# TamagotchiMainBoard.net
KiCad netlist of a schematic drawn in Altium Designer
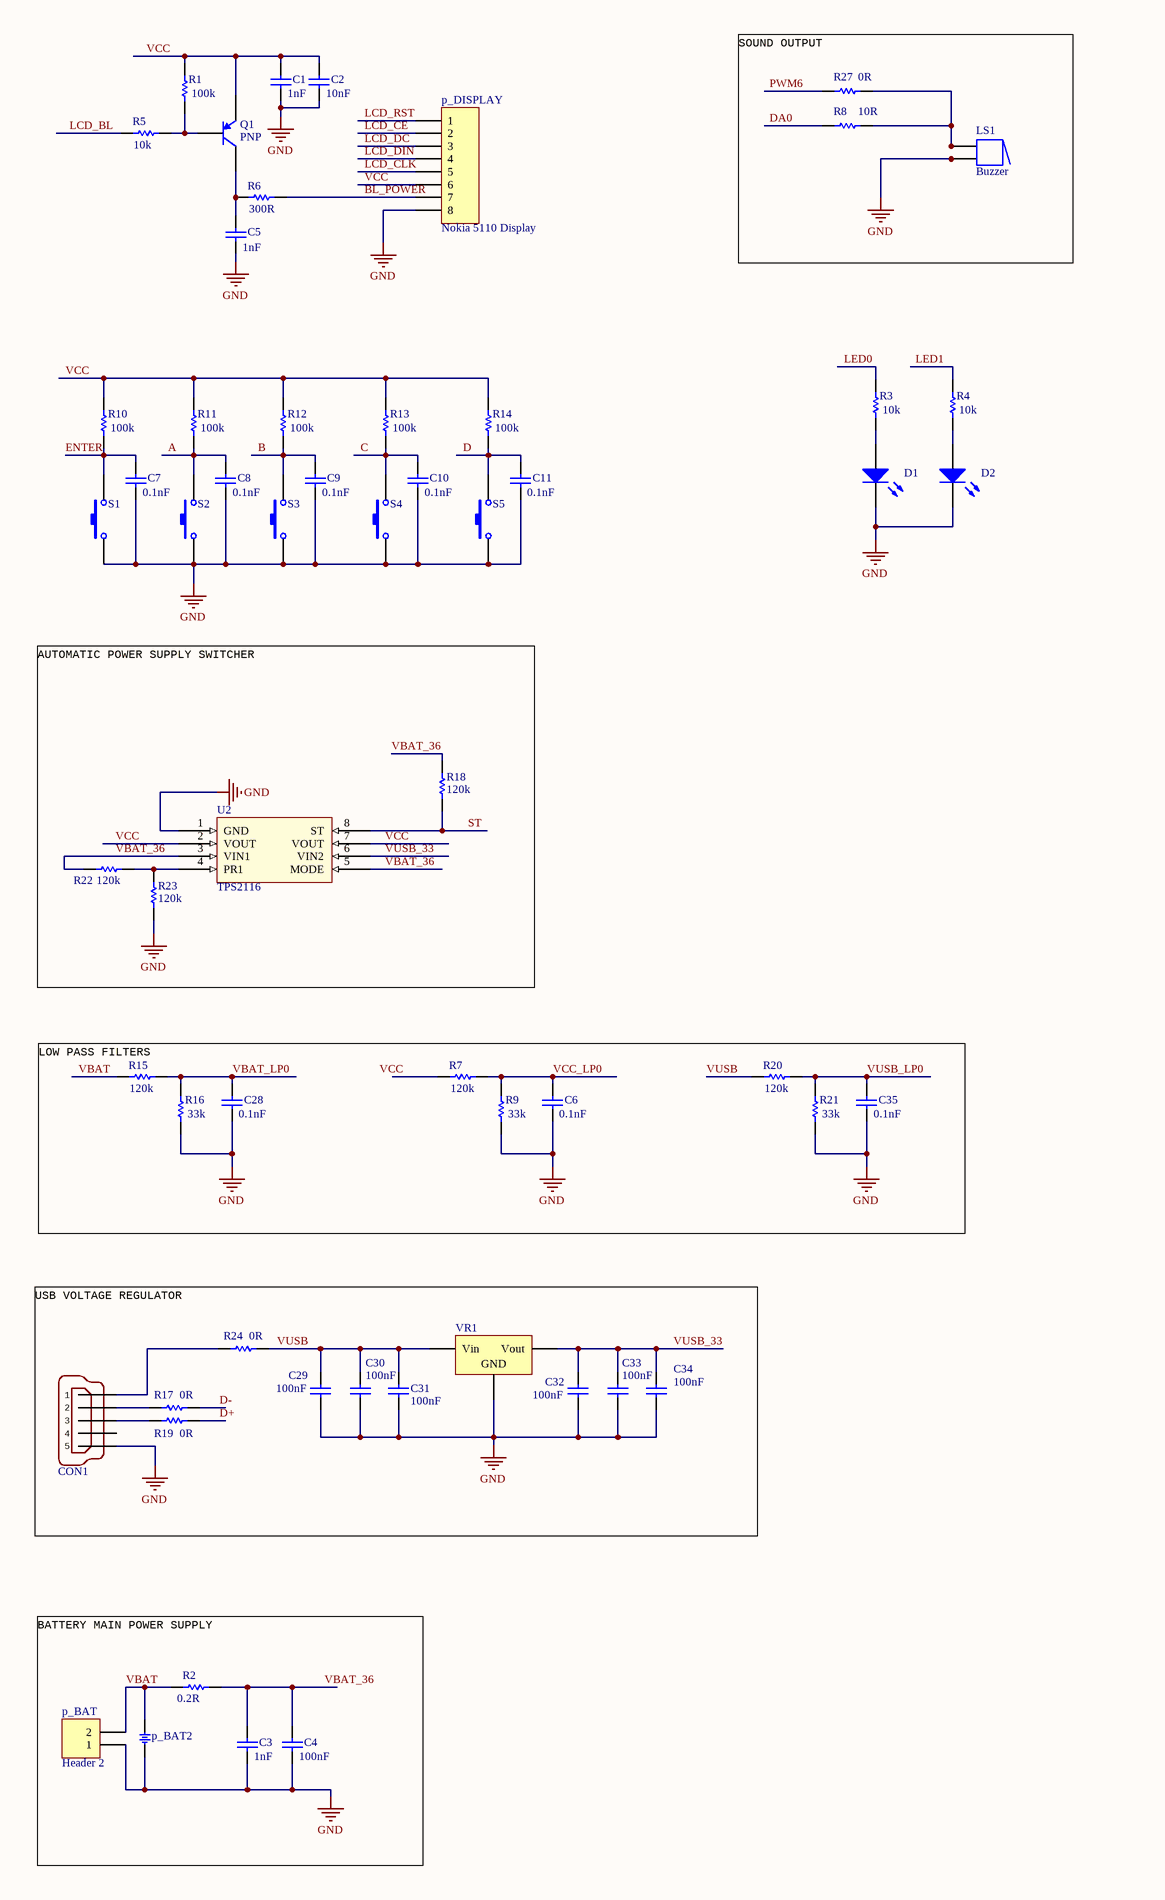
[diagram p0: TamagotchiMainBoard.SchDoc, left]
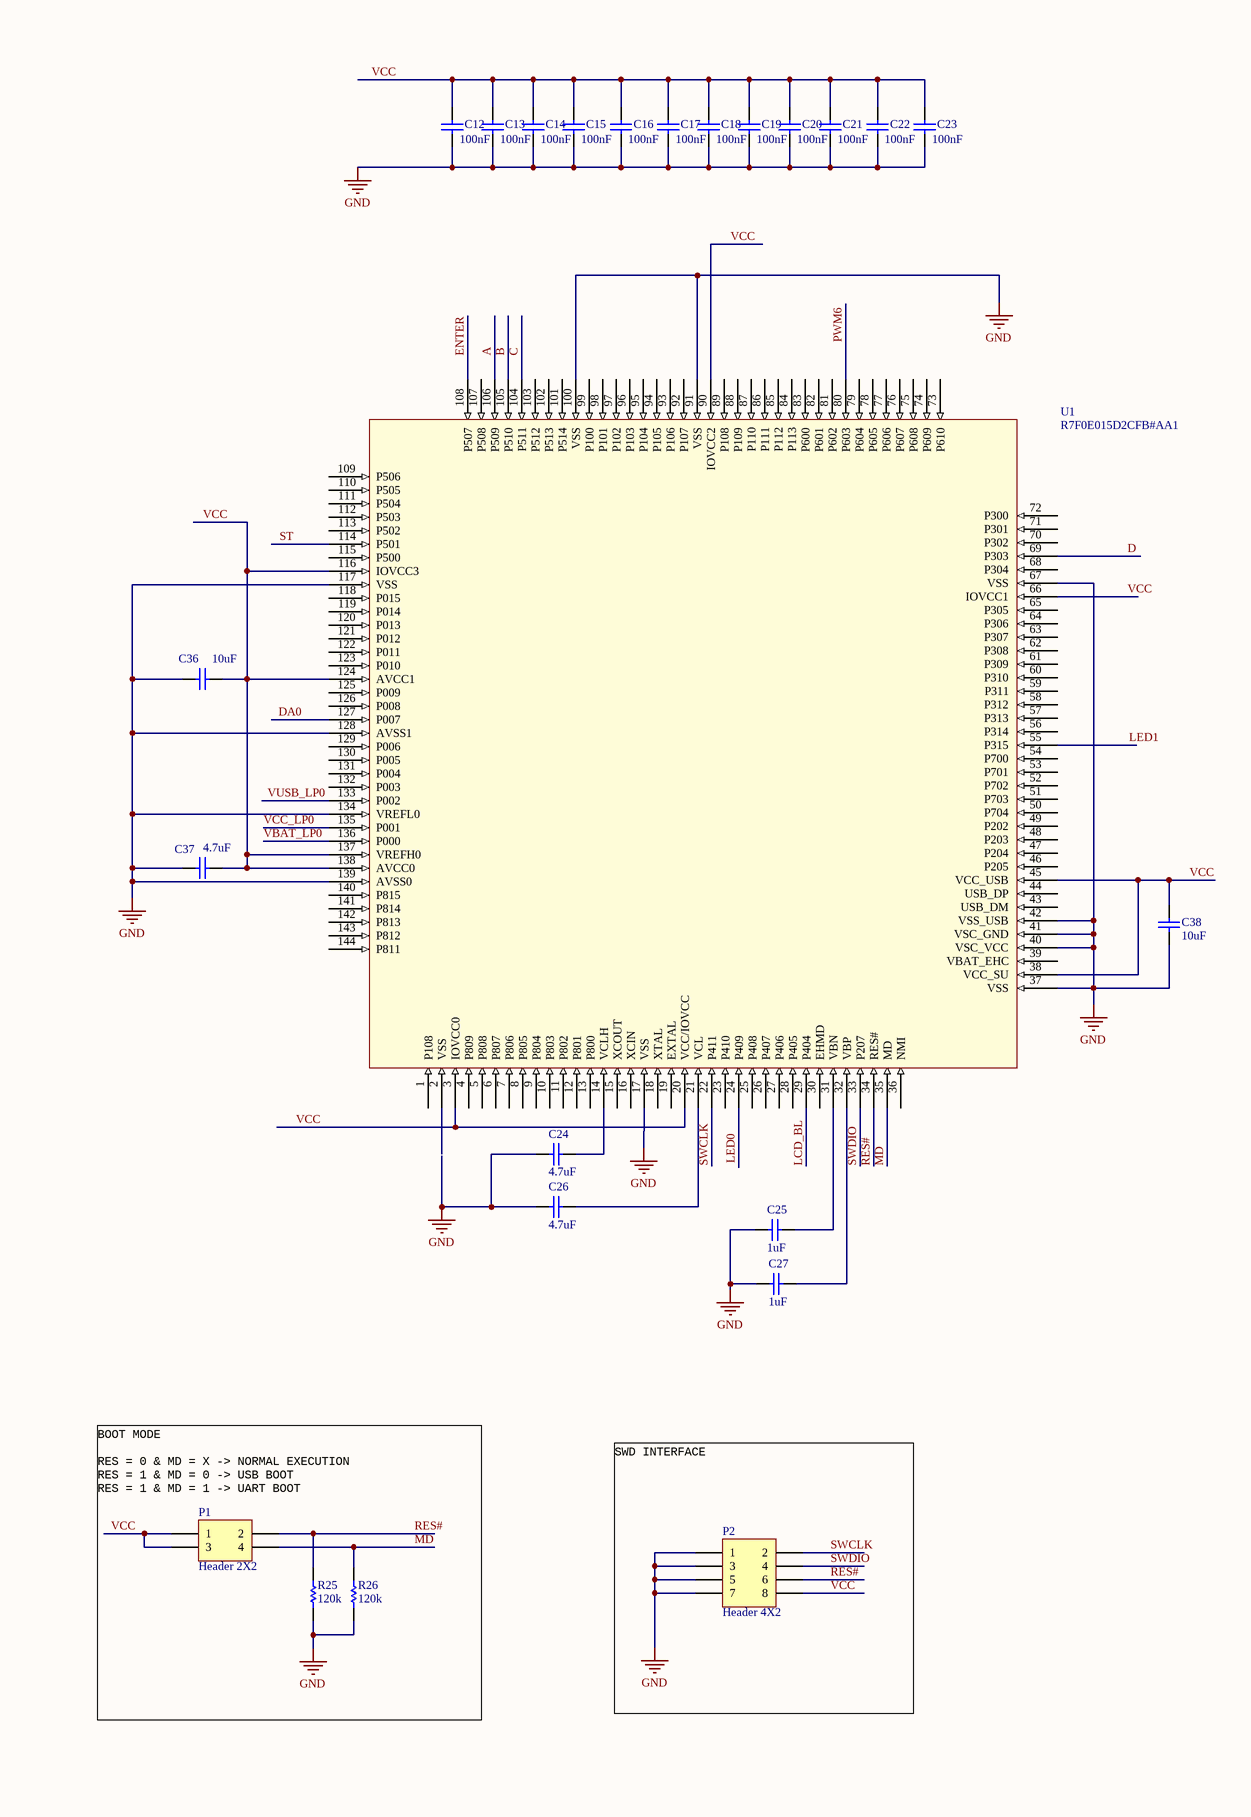
[diagram p1: TamagotchiMainBoard.SchDoc, right]

(export (version "E")
  (design (tool "Eeschema 10.0.6"))
  (components
    (comp (ref "C1")
      (value "1nF")
      (footprint "Miscellaneous Devices:C0805")
      (description "Capacitor")
      (fields (field (name "Comment") "Cap"))
      (libsource (lib "Miscellaneous Devices") (part "Cap"))
    )
    (comp (ref "C2")
      (value "10nF")
      (footprint "Miscellaneous Devices:C0805")
      (description "Capacitor")
      (fields (field (name "Comment") "Cap"))
      (libsource (lib "Miscellaneous Devices") (part "Cap"))
    )
    (comp (ref "C3")
      (value "1nF")
      (footprint "Miscellaneous Devices:C0805")
      (description "Capacitor")
      (fields (field (name "Comment") "Cap"))
      (libsource (lib "Miscellaneous Devices") (part "Cap"))
    )
    (comp (ref "C4")
      (value "100nF")
      (footprint "Miscellaneous Devices:C0805")
      (description "Capacitor")
      (fields (field (name "Comment") "Cap"))
      (libsource (lib "Miscellaneous Devices") (part "Cap"))
    )
    (comp (ref "C5")
      (value "1nF")
      (footprint "Miscellaneous Devices:C0805")
      (description "Capacitor")
      (fields (field (name "Comment") "Cap"))
      (libsource (lib "Miscellaneous Devices") (part "Cap"))
    )
    (comp (ref "C6")
      (value "0.1nF")
      (footprint "Miscellaneous Devices:C0805")
      (description "Capacitor")
      (fields (field (name "Comment") "Cap"))
      (libsource (lib "Miscellaneous Devices") (part "Cap"))
    )
    (comp (ref "C7")
      (value "0.1nF")
      (footprint "Miscellaneous Devices:C0805")
      (description "Capacitor")
      (fields (field (name "Comment") "Cap"))
      (libsource (lib "Miscellaneous Devices") (part "Cap"))
    )
    (comp (ref "C8")
      (value "0.1nF")
      (footprint "Miscellaneous Devices:C0805")
      (description "Capacitor")
      (fields (field (name "Comment") "Cap"))
      (libsource (lib "Miscellaneous Devices") (part "Cap"))
    )
    (comp (ref "C9")
      (value "0.1nF")
      (footprint "Miscellaneous Devices:C0805")
      (description "Capacitor")
      (fields (field (name "Comment") "Cap"))
      (libsource (lib "Miscellaneous Devices") (part "Cap"))
    )
    (comp (ref "C10")
      (value "0.1nF")
      (footprint "Miscellaneous Devices:C0805")
      (description "Capacitor")
      (fields (field (name "Comment") "Cap"))
      (libsource (lib "Miscellaneous Devices") (part "Cap"))
    )
    (comp (ref "C11")
      (value "0.1nF")
      (footprint "Miscellaneous Devices:C0805")
      (description "Capacitor")
      (fields (field (name "Comment") "Cap"))
      (libsource (lib "Miscellaneous Devices") (part "Cap"))
    )
    (comp (ref "C12")
      (value "100nF")
      (footprint "Miscellaneous Devices:C0805")
      (description "Capacitor")
      (fields (field (name "Comment") "Cap"))
      (libsource (lib "Miscellaneous Devices") (part "Cap"))
    )
    (comp (ref "C13")
      (value "100nF")
      (footprint "Miscellaneous Devices:C0805")
      (description "Capacitor")
      (fields (field (name "Comment") "Cap"))
      (libsource (lib "Miscellaneous Devices") (part "Cap"))
    )
    (comp (ref "C14")
      (value "100nF")
      (footprint "Miscellaneous Devices:C0805")
      (description "Capacitor")
      (fields (field (name "Comment") "Cap"))
      (libsource (lib "Miscellaneous Devices") (part "Cap"))
    )
    (comp (ref "C15")
      (value "100nF")
      (footprint "Miscellaneous Devices:C0805")
      (description "Capacitor")
      (fields (field (name "Comment") "Cap"))
      (libsource (lib "Miscellaneous Devices") (part "Cap"))
    )
    (comp (ref "C16")
      (value "100nF")
      (footprint "Miscellaneous Devices:C0805")
      (description "Capacitor")
      (fields (field (name "Comment") "Cap"))
      (libsource (lib "Miscellaneous Devices") (part "Cap"))
    )
    (comp (ref "C17")
      (value "100nF")
      (footprint "Miscellaneous Devices:C0805")
      (description "Capacitor")
      (fields (field (name "Comment") "Cap"))
      (libsource (lib "Miscellaneous Devices") (part "Cap"))
    )
    (comp (ref "C18")
      (value "100nF")
      (footprint "Miscellaneous Devices:C0805")
      (description "Capacitor")
      (fields (field (name "Comment") "Cap"))
      (libsource (lib "Miscellaneous Devices") (part "Cap"))
    )
    (comp (ref "C19")
      (value "100nF")
      (footprint "Miscellaneous Devices:C0805")
      (description "Capacitor")
      (fields (field (name "Comment") "Cap"))
      (libsource (lib "Miscellaneous Devices") (part "Cap"))
    )
    (comp (ref "C20")
      (value "100nF")
      (footprint "Miscellaneous Devices:C0805")
      (description "Capacitor")
      (fields (field (name "Comment") "Cap"))
      (libsource (lib "Miscellaneous Devices") (part "Cap"))
    )
    (comp (ref "C21")
      (value "100nF")
      (footprint "Miscellaneous Devices:C0805")
      (description "Capacitor")
      (fields (field (name "Comment") "Cap"))
      (libsource (lib "Miscellaneous Devices") (part "Cap"))
    )
    (comp (ref "C22")
      (value "100nF")
      (footprint "Miscellaneous Devices:C0805")
      (description "Capacitor")
      (fields (field (name "Comment") "Cap"))
      (libsource (lib "Miscellaneous Devices") (part "Cap"))
    )
    (comp (ref "C23")
      (value "100nF")
      (footprint "Miscellaneous Devices:C0805")
      (description "Capacitor")
      (fields (field (name "Comment") "Cap"))
      (libsource (lib "Miscellaneous Devices") (part "Cap"))
    )
    (comp (ref "C24")
      (value "4.7uF")
      (footprint "Miscellaneous Devices:C1206")
      (description "Capacitor")
      (fields (field (name "Comment") "Cap"))
      (libsource (lib "Miscellaneous Devices") (part "Cap"))
    )
    (comp (ref "C25")
      (value "1uF")
      (footprint "Miscellaneous Devices:C0805")
      (description "Capacitor")
      (fields (field (name "Comment") "Cap"))
      (libsource (lib "Miscellaneous Devices") (part "Cap"))
    )
    (comp (ref "C26")
      (value "4.7uF")
      (footprint "Miscellaneous Devices:C1206")
      (description "Capacitor")
      (fields (field (name "Comment") "Cap"))
      (libsource (lib "Miscellaneous Devices") (part "Cap"))
    )
    (comp (ref "C27")
      (value "1uF")
      (footprint "Miscellaneous Devices:C0805")
      (description "Capacitor")
      (fields (field (name "Comment") "Cap"))
      (libsource (lib "Miscellaneous Devices") (part "Cap"))
    )
    (comp (ref "C28")
      (value "0.1nF")
      (footprint "Miscellaneous Devices:C0805")
      (description "Capacitor")
      (fields (field (name "Comment") "Cap"))
      (libsource (lib "Miscellaneous Devices") (part "Cap"))
    )
    (comp (ref "C29")
      (value "100nF")
      (footprint "Miscellaneous Devices:C0805")
      (description "Capacitor")
      (fields (field (name "Comment") "Cap"))
      (libsource (lib "Miscellaneous Devices") (part "Cap"))
    )
    (comp (ref "C30")
      (value "100nF")
      (footprint "Miscellaneous Devices:C0805")
      (description "Capacitor")
      (fields (field (name "Comment") "Cap"))
      (libsource (lib "Miscellaneous Devices") (part "Cap"))
    )
    (comp (ref "C31")
      (value "100nF")
      (footprint "Miscellaneous Devices:C0805")
      (description "Capacitor")
      (fields (field (name "Comment") "Cap"))
      (libsource (lib "Miscellaneous Devices") (part "Cap"))
    )
    (comp (ref "C32")
      (value "100nF")
      (footprint "Miscellaneous Devices:C0805")
      (description "Capacitor")
      (fields (field (name "Comment") "Cap"))
      (libsource (lib "Miscellaneous Devices") (part "Cap"))
    )
    (comp (ref "C33")
      (value "100nF")
      (footprint "Miscellaneous Devices:C0805")
      (description "Capacitor")
      (fields (field (name "Comment") "Cap"))
      (libsource (lib "Miscellaneous Devices") (part "Cap"))
    )
    (comp (ref "C34")
      (value "100nF")
      (footprint "Miscellaneous Devices:C0805")
      (description "Capacitor")
      (fields (field (name "Comment") "Cap"))
      (libsource (lib "Miscellaneous Devices") (part "Cap"))
    )
    (comp (ref "C35")
      (value "0.1nF")
      (footprint "Miscellaneous Devices:C0805")
      (description "Capacitor")
      (fields (field (name "Comment") "Cap"))
      (libsource (lib "Miscellaneous Devices") (part "Cap"))
    )
    (comp (ref "C36")
      (value "10uF")
      (footprint "Miscellaneous Devices:C1206")
      (description "Capacitor")
      (fields (field (name "Comment") "Cap"))
      (libsource (lib "Miscellaneous Devices") (part "Cap"))
    )
    (comp (ref "C37")
      (value "4.7uF")
      (footprint "Miscellaneous Devices:C1206")
      (description "Capacitor")
      (fields (field (name "Comment") "Cap"))
      (libsource (lib "Miscellaneous Devices") (part "Cap"))
    )
    (comp (ref "C38")
      (value "10uF")
      (footprint "Miscellaneous Devices:C1206")
      (description "Capacitor")
      (fields (field (name "Comment") "Cap"))
      (libsource (lib "Miscellaneous Devices") (part "Cap"))
    )
    (comp (ref "CON1")
      (value "897-43-005-00-100001")
      (footprint "USB-MINI-B-5P-SMD")
      (description "Connector,MiniUSB B port,5 position,Right Angle,Gold flash 30u,black,SMD")
      (fields (field (name "MANUFACTURER") "MILL-MAX"))
      (libsource (lib "LAUNCHXL-F28379D_REV2.0") (part "MINI-USB-32005-201"))
    )
    (comp (ref "D1")
      (value "LED0")
      (description "Typical INFRARED GaAs LED")
      (libsource (lib "Miscellaneous Devices") (part "LED0"))
    )
    (comp (ref "D2")
      (value "LED0")
      (description "Typical INFRARED GaAs LED")
      (libsource (lib "Miscellaneous Devices") (part "LED0"))
    )
    (comp (ref "LS1")
      (value "Buzzer")
      (footprint "HDR1X2")
      (description "Magnetic Transducer Buzzer")
      (libsource (lib "Miscellaneous Devices") (part "Buzzer"))
    )
    (comp (ref "P1")
      (value "Header 2X2")
      (footprint "HDR2X2")
      (description "Header, 2-Pin, Dual row")
      (libsource (lib "Miscellaneous Connectors") (part "Header 2X2"))
    )
    (comp (ref "P2")
      (value "Header 4X2")
      (footprint "HDR2X4")
      (description "Header, 4-Pin, Dual row")
      (libsource (lib "Miscellaneous Connectors") (part "Header 4X2"))
    )
    (comp (ref "p_BAT")
      (value "Header 2")
      (footprint "HDR1X2")
      (description "Header, 2-Pin")
      (libsource (lib "Miscellaneous Connectors") (part "Header 2"))
    )
    (comp (ref "p_BAT2")
      (value "~")
      (footprint "BTH2032")
      (description "BATTERY HOLDER, CR2032")
      (libsource (lib "BTH2032") (part "BATH_CR2032"))
    )
    (comp (ref "p_DISPLAY")
      (value "Nokia 5110 Display")
      (footprint "HDR1X8")
      (description "Header, 8-Pin")
      (libsource (lib "Miscellaneous Connectors") (part "Header 8"))
    )
    (comp (ref "Q1")
      (value "PNP")
      (footprint "SOT-23B_N")
      (description "PNP Bipolar Transistor")
      (libsource (lib "Miscellaneous Devices") (part "PNP"))
    )
    (comp (ref "R1")
      (value "100k")
      (footprint "6-0805_M")
      (description "Resistor")
      (fields (field (name "Comment") "Res1"))
      (libsource (lib "Miscellaneous Devices") (part "Res1"))
    )
    (comp (ref "R2")
      (value "0.2R")
      (footprint "6-0805_M")
      (description "Resistor")
      (fields (field (name "Comment") "Res1"))
      (libsource (lib "Miscellaneous Devices") (part "Res1"))
    )
    (comp (ref "R3")
      (value "10k")
      (footprint "6-0805_M")
      (description "Resistor")
      (fields (field (name "Comment") "Res1"))
      (libsource (lib "Miscellaneous Devices") (part "Res1"))
    )
    (comp (ref "R4")
      (value "10k")
      (footprint "6-0805_M")
      (description "Resistor")
      (fields (field (name "Comment") "Res1"))
      (libsource (lib "Miscellaneous Devices") (part "Res1"))
    )
    (comp (ref "R5")
      (value "10k")
      (footprint "6-0805_M")
      (description "Resistor")
      (fields (field (name "Comment") "Res1"))
      (libsource (lib "Miscellaneous Devices") (part "Res1"))
    )
    (comp (ref "R6")
      (value "300R")
      (footprint "6-0805_M")
      (description "Resistor")
      (fields (field (name "Comment") "Res1"))
      (libsource (lib "Miscellaneous Devices") (part "Res1"))
    )
    (comp (ref "R7")
      (value "120k")
      (footprint "6-0805_M")
      (description "Resistor")
      (fields (field (name "Comment") "Res1"))
      (libsource (lib "Miscellaneous Devices") (part "Res1"))
    )
    (comp (ref "R8")
      (value "10R")
      (footprint "6-0805_M")
      (description "Resistor")
      (fields (field (name "Comment") "Res1"))
      (libsource (lib "Miscellaneous Devices") (part "Res1"))
    )
    (comp (ref "R9")
      (value "33k")
      (footprint "6-0805_M")
      (description "Resistor")
      (fields (field (name "Comment") "Res1"))
      (libsource (lib "Miscellaneous Devices") (part "Res1"))
    )
    (comp (ref "R10")
      (value "100k")
      (footprint "6-0805_M")
      (description "Resistor")
      (fields (field (name "Comment") "Res1"))
      (libsource (lib "Miscellaneous Devices") (part "Res1"))
    )
    (comp (ref "R11")
      (value "100k")
      (footprint "6-0805_M")
      (description "Resistor")
      (fields (field (name "Comment") "Res1"))
      (libsource (lib "Miscellaneous Devices") (part "Res1"))
    )
    (comp (ref "R12")
      (value "100k")
      (footprint "6-0805_M")
      (description "Resistor")
      (fields (field (name "Comment") "Res1"))
      (libsource (lib "Miscellaneous Devices") (part "Res1"))
    )
    (comp (ref "R13")
      (value "100k")
      (footprint "6-0805_M")
      (description "Resistor")
      (fields (field (name "Comment") "Res1"))
      (libsource (lib "Miscellaneous Devices") (part "Res1"))
    )
    (comp (ref "R14")
      (value "100k")
      (footprint "6-0805_M")
      (description "Resistor")
      (fields (field (name "Comment") "Res1"))
      (libsource (lib "Miscellaneous Devices") (part "Res1"))
    )
    (comp (ref "R15")
      (value "120k")
      (footprint "6-0805_M")
      (description "Resistor")
      (fields (field (name "Comment") "Res1"))
      (libsource (lib "Miscellaneous Devices") (part "Res1"))
    )
    (comp (ref "R16")
      (value "33k")
      (footprint "6-0805_M")
      (description "Resistor")
      (fields (field (name "Comment") "Res1"))
      (libsource (lib "Miscellaneous Devices") (part "Res1"))
    )
    (comp (ref "R17")
      (value "0R")
      (footprint "6-0805_M")
      (description "Resistor")
      (libsource (lib "Miscellaneous Devices") (part "Res1"))
    )
    (comp (ref "R18")
      (value "120k")
      (footprint "6-0805_M")
      (description "Resistor")
      (fields (field (name "Comment") "Res1"))
      (libsource (lib "Miscellaneous Devices") (part "Res1"))
    )
    (comp (ref "R19")
      (value "0R")
      (footprint "6-0805_M")
      (description "Resistor")
      (libsource (lib "Miscellaneous Devices") (part "Res1"))
    )
    (comp (ref "R20")
      (value "120k")
      (footprint "6-0805_M")
      (description "Resistor")
      (fields (field (name "Comment") "Res1"))
      (libsource (lib "Miscellaneous Devices") (part "Res1"))
    )
    (comp (ref "R21")
      (value "33k")
      (footprint "6-0805_M")
      (description "Resistor")
      (fields (field (name "Comment") "Res1"))
      (libsource (lib "Miscellaneous Devices") (part "Res1"))
    )
    (comp (ref "R22")
      (value "120k")
      (footprint "6-0805_M")
      (description "Resistor")
      (fields (field (name "Comment") "Res1"))
      (libsource (lib "Miscellaneous Devices") (part "Res1"))
    )
    (comp (ref "R23")
      (value "120k")
      (footprint "6-0805_M")
      (description "Resistor")
      (fields (field (name "Comment") "Res1"))
      (libsource (lib "Miscellaneous Devices") (part "Res1"))
    )
    (comp (ref "R24")
      (value "0R")
      (footprint "6-0805_M")
      (description "Resistor")
      (libsource (lib "Miscellaneous Devices") (part "Res1"))
    )
    (comp (ref "R25")
      (value "120k")
      (footprint "6-0805_M")
      (description "Resistor")
      (fields (field (name "Comment") "Res1"))
      (libsource (lib "Miscellaneous Devices") (part "Res1"))
    )
    (comp (ref "R26")
      (value "120k")
      (footprint "6-0805_M")
      (description "Resistor")
      (fields (field (name "Comment") "Res1"))
      (libsource (lib "Miscellaneous Devices") (part "Res1"))
    )
    (comp (ref "R27")
      (value "0R")
      (footprint "6-0805_M")
      (description "Resistor")
      (fields (field (name "Comment") "Res1"))
      (libsource (lib "Miscellaneous Devices") (part "Res1"))
    )
    (comp (ref "S1")
      (value "SW-PB")
      (footprint "SPST-2")
      (description "Switch")
      (libsource (lib "Miscellaneous Devices") (part "SW-PB"))
    )
    (comp (ref "S2")
      (value "SW-PB")
      (footprint "SPST-2")
      (description "Switch")
      (libsource (lib "Miscellaneous Devices") (part "SW-PB"))
    )
    (comp (ref "S3")
      (value "SW-PB")
      (footprint "SPST-2")
      (description "Switch")
      (libsource (lib "Miscellaneous Devices") (part "SW-PB"))
    )
    (comp (ref "S4")
      (value "SW-PB")
      (footprint "SPST-2")
      (description "Switch")
      (libsource (lib "Miscellaneous Devices") (part "SW-PB"))
    )
    (comp (ref "S5")
      (value "SW-PB")
      (footprint "SPST-2")
      (description "Switch")
      (libsource (lib "Miscellaneous Devices") (part "SW-PB"))
    )
    (comp (ref "U1")
      (value "R7F0E015D2CFB#AA1")
      (footprint "SQFP50P2200X2200X170-144N")
      (description "ARM® Cortex®-M0+ series Microcontroller IC 32-Bit 24MHz 1.5MB (1.5M x 8) FLASH 144-LFQFP (20x20)")
      (libsource (lib "YamagotchiLib") (part "R7F0E015D2CFB#AA1"))
    )
    (comp (ref "U2")
      (value "TPS2116")
      (description "TPS2116 1.6 V to 5.5 V, 2.5-A Low IQ Power Mux with Manual and Priority Switchover")
      (libsource (lib "YamagotchiLib") (part "TPS2116"))
    )
    (comp (ref "VR1")
      (value "Volt Reg")
      (footprint "D2PAK_N")
      (description "Voltage Regulator")
      (libsource (lib "Miscellaneous Devices") (part "Volt Reg"))
    )
  )
  (nets
    (net (code "1") (name "/A") (class "Default")
      (node (ref "C8") (pin "1") (pinfunction "1_1") (pintype "passive"))
      (node (ref "R11") (pin "2") (pinfunction "2_2") (pintype "passive"))
      (node (ref "S2") (pin "2") (pinfunction "2_2") (pintype "passive"))
      (node (ref "U1") (pin "106") (pinfunction "P509_106") (pintype "input"))
    )
    (net (code "2") (name "/B") (class "Default")
      (node (ref "C9") (pin "1") (pinfunction "1_1") (pintype "passive"))
      (node (ref "R12") (pin "2") (pinfunction "2_2") (pintype "passive"))
      (node (ref "S3") (pin "2") (pinfunction "2_2") (pintype "passive"))
      (node (ref "U1") (pin "105") (pinfunction "P510_105") (pintype "input"))
    )
    (net (code "3") (name "/BL_POWER") (class "Default")
      (node (ref "R6") (pin "1") (pinfunction "1_1") (pintype "passive"))
      (node (ref "p_DISPLAY") (pin "7") (pinfunction "7_7") (pintype "passive"))
    )
    (net (code "4") (name "/C") (class "Default")
      (node (ref "C10") (pin "1") (pinfunction "1_1") (pintype "passive"))
      (node (ref "R13") (pin "2") (pinfunction "2_2") (pintype "passive"))
      (node (ref "S4") (pin "2") (pinfunction "2_2") (pintype "passive"))
      (node (ref "U1") (pin "104") (pinfunction "P511_104") (pintype "input"))
    )
    (net (code "5") (name "/D") (class "Default")
      (node (ref "C11") (pin "1") (pinfunction "1_1") (pintype "passive"))
      (node (ref "R14") (pin "2") (pinfunction "2_2") (pintype "passive"))
      (node (ref "S5") (pin "2") (pinfunction "2_2") (pintype "passive"))
      (node (ref "U1") (pin "69") (pinfunction "P303_69") (pintype "input"))
    )
    (net (code "6") (name "/D+") (class "Default")
      (node (ref "R19") (pin "1") (pinfunction "1_1") (pintype "passive"))
    )
    (net (code "7") (name "/D-") (class "Default")
      (node (ref "R17") (pin "1") (pinfunction "1_1") (pintype "passive"))
    )
    (net (code "8") (name "/DA0") (class "Default")
      (node (ref "R8") (pin "1") (pinfunction "1_1") (pintype "passive"))
      (node (ref "U1") (pin "127") (pinfunction "P007_127") (pintype "input"))
    )
    (net (code "9") (name "/ENTER") (class "Default")
      (node (ref "C7") (pin "1") (pinfunction "1_1") (pintype "passive"))
      (node (ref "R10") (pin "2") (pinfunction "2_2") (pintype "passive"))
      (node (ref "S1") (pin "2") (pinfunction "2_2") (pintype "passive"))
      (node (ref "U1") (pin "108") (pinfunction "P507_108") (pintype "input"))
    )
    (net (code "10") (name "/LCD_BL") (class "Default")
      (node (ref "R5") (pin "2") (pinfunction "2_2") (pintype "passive"))
      (node (ref "U1") (pin "29") (pinfunction "P404_29") (pintype "input"))
    )
    (net (code "11") (name "/LCD_CE") (class "Default")
      (node (ref "p_DISPLAY") (pin "2") (pinfunction "2_2") (pintype "passive"))
    )
    (net (code "12") (name "/LCD_CLK") (class "Default")
      (node (ref "p_DISPLAY") (pin "5") (pinfunction "5_5") (pintype "passive"))
    )
    (net (code "13") (name "/LCD_DC") (class "Default")
      (node (ref "p_DISPLAY") (pin "3") (pinfunction "3_3") (pintype "passive"))
    )
    (net (code "14") (name "/LCD_DIN") (class "Default")
      (node (ref "p_DISPLAY") (pin "4") (pinfunction "4_4") (pintype "passive"))
    )
    (net (code "15") (name "/LCD_RST") (class "Default")
      (node (ref "p_DISPLAY") (pin "1") (pinfunction "1_1") (pintype "passive"))
    )
    (net (code "16") (name "/LED0") (class "Default")
      (node (ref "R3") (pin "1") (pinfunction "1_1") (pintype "passive"))
      (node (ref "U1") (pin "24") (pinfunction "P409_24") (pintype "input"))
    )
    (net (code "17") (name "/LED1") (class "Default")
      (node (ref "R4") (pin "1") (pinfunction "1_1") (pintype "passive"))
      (node (ref "U1") (pin "55") (pinfunction "P315_55") (pintype "input"))
    )
    (net (code "18") (name "/MD") (class "Default")
      (node (ref "P1") (pin "4") (pinfunction "4_4") (pintype "passive"))
      (node (ref "R26") (pin "1") (pinfunction "1_1") (pintype "passive"))
      (node (ref "U1") (pin "35") (pinfunction "MD_35") (pintype "input"))
    )
    (net (code "19") (name "/PWM6") (class "Default")
      (node (ref "R27") (pin "1") (pinfunction "1_1") (pintype "passive"))
      (node (ref "U1") (pin "80") (pinfunction "P603_80") (pintype "input"))
    )
    (net (code "20") (name "/RES#") (class "Default")
      (node (ref "P1") (pin "2") (pinfunction "2_2") (pintype "passive"))
      (node (ref "P2") (pin "6") (pinfunction "6_6") (pintype "passive"))
      (node (ref "R25") (pin "1") (pinfunction "1_1") (pintype "passive"))
      (node (ref "U1") (pin "34") (pinfunction "RES#_34") (pintype "input"))
    )
    (net (code "21") (name "/ST") (class "Default")
      (node (ref "R18") (pin "2") (pinfunction "2_2") (pintype "passive"))
      (node (ref "U1") (pin "114") (pinfunction "P501_114") (pintype "input"))
      (node (ref "U2") (pin "8") (pinfunction "ST_8") (pintype "input"))
    )
    (net (code "22") (name "/SWCLK") (class "Default")
      (node (ref "P2") (pin "2") (pinfunction "2_2") (pintype "passive"))
      (node (ref "U1") (pin "22") (pinfunction "P411_22") (pintype "input"))
    )
    (net (code "23") (name "/SWDIO") (class "Default")
      (node (ref "P2") (pin "4") (pinfunction "4_4") (pintype "passive"))
      (node (ref "U1") (pin "33") (pinfunction "P207_33") (pintype "input"))
    )
    (net (code "24") (name "/VBAT") (class "Default")
      (node (ref "R15") (pin "2") (pinfunction "2_2") (pintype "passive"))
      (node (ref "R2") (pin "2") (pinfunction "2_2") (pintype "passive"))
      (node (ref "p_BAT") (pin "2") (pinfunction "2_2") (pintype "passive"))
      (node (ref "p_BAT2") (pin "1") (pinfunction "1_1") (pintype "passive"))
    )
    (net (code "25") (name "/VBAT_36") (class "Default")
      (node (ref "C3") (pin "2") (pinfunction "2_2") (pintype "passive"))
      (node (ref "C4") (pin "2") (pinfunction "2_2") (pintype "passive"))
      (node (ref "R18") (pin "1") (pinfunction "1_1") (pintype "passive"))
      (node (ref "R2") (pin "1") (pinfunction "1_1") (pintype "passive"))
      (node (ref "R22") (pin "1") (pinfunction "1_1") (pintype "passive"))
      (node (ref "U2") (pin "3") (pinfunction "VIN1_3") (pintype "input"))
      (node (ref "U2") (pin "5") (pinfunction "MODE_5") (pintype "input"))
    )
    (net (code "26") (name "/VBAT_LP0") (class "Default")
      (node (ref "C28") (pin "1") (pinfunction "1_1") (pintype "passive"))
      (node (ref "R15") (pin "1") (pinfunction "1_1") (pintype "passive"))
      (node (ref "R16") (pin "1") (pinfunction "1_1") (pintype "passive"))
      (node (ref "U1") (pin "136") (pinfunction "P000_136") (pintype "input"))
    )
    (net (code "27") (name "/VCC") (class "Default")
      (node (ref "C1") (pin "2") (pinfunction "2_2") (pintype "passive"))
      (node (ref "C12") (pin "2") (pinfunction "2_2") (pintype "passive"))
      (node (ref "C13") (pin "2") (pinfunction "2_2") (pintype "passive"))
      (node (ref "C14") (pin "2") (pinfunction "2_2") (pintype "passive"))
      (node (ref "C15") (pin "2") (pinfunction "2_2") (pintype "passive"))
      (node (ref "C16") (pin "2") (pinfunction "2_2") (pintype "passive"))
      (node (ref "C17") (pin "2") (pinfunction "2_2") (pintype "passive"))
      (node (ref "C18") (pin "2") (pinfunction "2_2") (pintype "passive"))
      (node (ref "C19") (pin "2") (pinfunction "2_2") (pintype "passive"))
      (node (ref "C2") (pin "2") (pinfunction "2_2") (pintype "passive"))
      (node (ref "C20") (pin "2") (pinfunction "2_2") (pintype "passive"))
      (node (ref "C21") (pin "2") (pinfunction "2_2") (pintype "passive"))
      (node (ref "C22") (pin "2") (pinfunction "2_2") (pintype "passive"))
      (node (ref "C23") (pin "2") (pinfunction "2_2") (pintype "passive"))
      (node (ref "C36") (pin "1") (pinfunction "1_1") (pintype "passive"))
      (node (ref "C37") (pin "1") (pinfunction "1_1") (pintype "passive"))
      (node (ref "C38") (pin "2") (pinfunction "2_2") (pintype "passive"))
      (node (ref "P1") (pin "1") (pinfunction "1_1") (pintype "passive"))
      (node (ref "P1") (pin "3") (pinfunction "3_3") (pintype "passive"))
      (node (ref "P2") (pin "8") (pinfunction "8_8") (pintype "passive"))
      (node (ref "Q1") (pin "3") (pinfunction "E_3") (pintype "passive"))
      (node (ref "R1") (pin "1") (pinfunction "1_1") (pintype "passive"))
      (node (ref "R10") (pin "1") (pinfunction "1_1") (pintype "passive"))
      (node (ref "R11") (pin "1") (pinfunction "1_1") (pintype "passive"))
      (node (ref "R12") (pin "1") (pinfunction "1_1") (pintype "passive"))
      (node (ref "R13") (pin "1") (pinfunction "1_1") (pintype "passive"))
      (node (ref "R14") (pin "1") (pinfunction "1_1") (pintype "passive"))
      (node (ref "U1") (pin "116") (pinfunction "IOVCC3_116") (pintype "input"))
      (node (ref "U1") (pin "124") (pinfunction "AVCC1_124") (pintype "input"))
      (node (ref "U1") (pin "137") (pinfunction "VREFH0_137") (pintype "input"))
      (node (ref "U1") (pin "138") (pinfunction "AVCC0_138") (pintype "input"))
      (node (ref "U1") (pin "20") (pinfunction "VCC/IOVCC_20") (pintype "input"))
      (node (ref "U1") (pin "3") (pinfunction "IOVCC0_3") (pintype "input"))
      (node (ref "U1") (pin "38") (pinfunction "VCC_SU_38") (pintype "input"))
      (node (ref "U1") (pin "45") (pinfunction "VCC_USB_45") (pintype "input"))
      (node (ref "U1") (pin "66") (pinfunction "IOVCC1_66") (pintype "input"))
      (node (ref "U1") (pin "90") (pinfunction "IOVCC2_90") (pintype "input"))
      (node (ref "U2") (pin "2") (pinfunction "VOUT_2") (pintype "input"))
      (node (ref "U2") (pin "7") (pinfunction "VOUT_7") (pintype "input"))
      (node (ref "p_DISPLAY") (pin "6") (pinfunction "6_6") (pintype "passive"))
    )
    (net (code "28") (name "/VCC_LP0") (class "Default")
      (node (ref "C6") (pin "1") (pinfunction "1_1") (pintype "passive"))
      (node (ref "R7") (pin "1") (pinfunction "1_1") (pintype "passive"))
      (node (ref "R9") (pin "1") (pinfunction "1_1") (pintype "passive"))
      (node (ref "U1") (pin "135") (pinfunction "P001_135") (pintype "input"))
    )
    (net (code "29") (name "/VUSB") (class "Default")
      (node (ref "C29") (pin "2") (pinfunction "2_2") (pintype "passive"))
      (node (ref "C30") (pin "2") (pinfunction "2_2") (pintype "passive"))
      (node (ref "C31") (pin "2") (pinfunction "2_2") (pintype "passive"))
      (node (ref "R20") (pin "2") (pinfunction "2_2") (pintype "passive"))
      (node (ref "R24") (pin "1") (pinfunction "1_1") (pintype "passive"))
      (node (ref "VR1") (pin "1") (pinfunction "Vin_1") (pintype "passive"))
    )
    (net (code "30") (name "/VUSB_33") (class "Default")
      (node (ref "C32") (pin "2") (pinfunction "2_2") (pintype "passive"))
      (node (ref "C33") (pin "2") (pinfunction "2_2") (pintype "passive"))
      (node (ref "C34") (pin "2") (pinfunction "2_2") (pintype "passive"))
      (node (ref "U2") (pin "6") (pinfunction "VIN2_6") (pintype "input"))
      (node (ref "VR1") (pin "3") (pinfunction "Vout_3") (pintype "passive"))
    )
    (net (code "31") (name "/VUSB_LP0") (class "Default")
      (node (ref "C35") (pin "1") (pinfunction "1_1") (pintype "passive"))
      (node (ref "R20") (pin "1") (pinfunction "1_1") (pintype "passive"))
      (node (ref "R21") (pin "1") (pinfunction "1_1") (pintype "passive"))
      (node (ref "U1") (pin "133") (pinfunction "P002_133") (pintype "input"))
    )
    (net (code "32") (name "GND") (class "Default")
      (node (ref "C1") (pin "1") (pinfunction "1_1") (pintype "passive"))
      (node (ref "C10") (pin "2") (pinfunction "2_2") (pintype "passive"))
      (node (ref "C11") (pin "2") (pinfunction "2_2") (pintype "passive"))
      (node (ref "C12") (pin "1") (pinfunction "1_1") (pintype "passive"))
      (node (ref "C13") (pin "1") (pinfunction "1_1") (pintype "passive"))
      (node (ref "C14") (pin "1") (pinfunction "1_1") (pintype "passive"))
      (node (ref "C15") (pin "1") (pinfunction "1_1") (pintype "passive"))
      (node (ref "C16") (pin "1") (pinfunction "1_1") (pintype "passive"))
      (node (ref "C17") (pin "1") (pinfunction "1_1") (pintype "passive"))
      (node (ref "C18") (pin "1") (pinfunction "1_1") (pintype "passive"))
      (node (ref "C19") (pin "1") (pinfunction "1_1") (pintype "passive"))
      (node (ref "C2") (pin "1") (pinfunction "1_1") (pintype "passive"))
      (node (ref "C20") (pin "1") (pinfunction "1_1") (pintype "passive"))
      (node (ref "C21") (pin "1") (pinfunction "1_1") (pintype "passive"))
      (node (ref "C22") (pin "1") (pinfunction "1_1") (pintype "passive"))
      (node (ref "C23") (pin "1") (pinfunction "1_1") (pintype "passive"))
      (node (ref "C24") (pin "2") (pinfunction "2_2") (pintype "passive"))
      (node (ref "C25") (pin "1") (pinfunction "1_1") (pintype "passive"))
      (node (ref "C26") (pin "2") (pinfunction "2_2") (pintype "passive"))
      (node (ref "C27") (pin "1") (pinfunction "1_1") (pintype "passive"))
      (node (ref "C28") (pin "2") (pinfunction "2_2") (pintype "passive"))
      (node (ref "C29") (pin "1") (pinfunction "1_1") (pintype "passive"))
      (node (ref "C3") (pin "1") (pinfunction "1_1") (pintype "passive"))
      (node (ref "C30") (pin "1") (pinfunction "1_1") (pintype "passive"))
      (node (ref "C31") (pin "1") (pinfunction "1_1") (pintype "passive"))
      (node (ref "C32") (pin "1") (pinfunction "1_1") (pintype "passive"))
      (node (ref "C33") (pin "1") (pinfunction "1_1") (pintype "passive"))
      (node (ref "C34") (pin "1") (pinfunction "1_1") (pintype "passive"))
      (node (ref "C35") (pin "2") (pinfunction "2_2") (pintype "passive"))
      (node (ref "C36") (pin "2") (pinfunction "2_2") (pintype "passive"))
      (node (ref "C37") (pin "2") (pinfunction "2_2") (pintype "passive"))
      (node (ref "C38") (pin "1") (pinfunction "1_1") (pintype "passive"))
      (node (ref "C4") (pin "1") (pinfunction "1_1") (pintype "passive"))
      (node (ref "C5") (pin "1") (pinfunction "1_1") (pintype "passive"))
      (node (ref "C6") (pin "2") (pinfunction "2_2") (pintype "passive"))
      (node (ref "C7") (pin "2") (pinfunction "2_2") (pintype "passive"))
      (node (ref "C8") (pin "2") (pinfunction "2_2") (pintype "passive"))
      (node (ref "C9") (pin "2") (pinfunction "2_2") (pintype "passive"))
      (node (ref "CON1") (pin "5") (pinfunction "5_5") (pintype "passive"))
      (node (ref "D1") (pin "2") (pinfunction "K_2") (pintype "passive"))
      (node (ref "D2") (pin "2") (pinfunction "K_2") (pintype "passive"))
      (node (ref "LS1") (pin "2") (pinfunction "2_2") (pintype "passive"))
      (node (ref "LS1") (pin "2A") (pinfunction "2A_2A") (pintype "passive"))
      (node (ref "P2") (pin "1") (pinfunction "1_1") (pintype "passive"))
      (node (ref "P2") (pin "3") (pinfunction "3_3") (pintype "passive"))
      (node (ref "P2") (pin "5") (pinfunction "5_5") (pintype "passive"))
      (node (ref "P2") (pin "7") (pinfunction "7_7") (pintype "passive"))
      (node (ref "R16") (pin "2") (pinfunction "2_2") (pintype "passive"))
      (node (ref "R21") (pin "2") (pinfunction "2_2") (pintype "passive"))
      (node (ref "R23") (pin "2") (pinfunction "2_2") (pintype "passive"))
      (node (ref "R25") (pin "2") (pinfunction "2_2") (pintype "passive"))
      (node (ref "R26") (pin "2") (pinfunction "2_2") (pintype "passive"))
      (node (ref "R9") (pin "2") (pinfunction "2_2") (pintype "passive"))
      (node (ref "S1") (pin "1") (pinfunction "1_1") (pintype "passive"))
      (node (ref "S2") (pin "1") (pinfunction "1_1") (pintype "passive"))
      (node (ref "S3") (pin "1") (pinfunction "1_1") (pintype "passive"))
      (node (ref "S4") (pin "1") (pinfunction "1_1") (pintype "passive"))
      (node (ref "S5") (pin "1") (pinfunction "1_1") (pintype "passive"))
      (node (ref "U1") (pin "100") (pinfunction "VSS_100") (pintype "input"))
      (node (ref "U1") (pin "117") (pinfunction "VSS_117") (pintype "input"))
      (node (ref "U1") (pin "128") (pinfunction "AVSS1_128") (pintype "input"))
      (node (ref "U1") (pin "134") (pinfunction "VREFL0_134") (pintype "input"))
      (node (ref "U1") (pin "139") (pinfunction "AVSS0_139") (pintype "input"))
      (node (ref "U1") (pin "17") (pinfunction "VSS_17") (pintype "input"))
      (node (ref "U1") (pin "37") (pinfunction "VSS_37") (pintype "input"))
      (node (ref "U1") (pin "40") (pinfunction "VSC_VCC_40") (pintype "input"))
      (node (ref "U1") (pin "41") (pinfunction "VSC_GND_41") (pintype "input"))
      (node (ref "U1") (pin "42") (pinfunction "VSS_USB_42") (pintype "input"))
      (node (ref "U1") (pin "67") (pinfunction "VSS_67") (pintype "input"))
      (node (ref "U1") (pin "91") (pinfunction "VSS_91") (pintype "input"))
      (node (ref "U2") (pin "1") (pinfunction "GND_1") (pintype "input"))
      (node (ref "VR1") (pin "2") (pinfunction "GND_2") (pintype "passive"))
      (node (ref "p_BAT") (pin "1") (pinfunction "1_1") (pintype "passive"))
      (node (ref "p_BAT2") (pin "2") (pinfunction "2_2") (pintype "passive"))
      (node (ref "p_DISPLAY") (pin "8") (pinfunction "8_8") (pintype "passive"))
    )
    (net (code "33") (name "Net-(CON1-Pad1)") (class "Default")
      (node (ref "CON1") (pin "1") (pinfunction "1_1") (pintype "passive"))
      (node (ref "R24") (pin "2") (pinfunction "2_2") (pintype "passive"))
    )
    (net (code "34") (name "Net-(CON1-Pad2)") (class "Default")
      (node (ref "CON1") (pin "2") (pinfunction "2_2") (pintype "passive"))
      (node (ref "R17") (pin "2") (pinfunction "2_2") (pintype "passive"))
    )
    (net (code "35") (name "Net-(CON1-Pad3)") (class "Default")
      (node (ref "CON1") (pin "3") (pinfunction "3_3") (pintype "passive"))
      (node (ref "R19") (pin "2") (pinfunction "2_2") (pintype "passive"))
    )
    (net (code "36") (name "Net-(D1-A)") (class "Default")
      (node (ref "D1") (pin "1") (pinfunction "A_1") (pintype "passive"))
      (node (ref "R3") (pin "2") (pinfunction "2_2") (pintype "passive"))
    )
    (net (code "37") (name "Net-(D2-A)") (class "Default")
      (node (ref "D2") (pin "1") (pinfunction "A_1") (pintype "passive"))
      (node (ref "R4") (pin "2") (pinfunction "2_2") (pintype "passive"))
    )
    (net (code "38") (name "Net-(LS1-Pad1)") (class "Default")
      (node (ref "LS1") (pin "1") (pinfunction "1_1") (pintype "passive"))
      (node (ref "LS1") (pin "1A") (pinfunction "1A_1A") (pintype "passive"))
      (node (ref "R27") (pin "2") (pinfunction "2_2") (pintype "passive"))
      (node (ref "R8") (pin "2") (pinfunction "2_2") (pintype "passive"))
    )
    (net (code "39") (name "Net-(Q1-B)") (class "Default")
      (node (ref "Q1") (pin "2") (pinfunction "B_2") (pintype "passive"))
      (node (ref "R1") (pin "2") (pinfunction "2_2") (pintype "passive"))
      (node (ref "R5") (pin "1") (pinfunction "1_1") (pintype "passive"))
    )
    (net (code "40") (name "Net-(Q1-C)") (class "Default")
      (node (ref "C5") (pin "2") (pinfunction "2_2") (pintype "passive"))
      (node (ref "Q1") (pin "1") (pinfunction "C_1") (pintype "passive"))
      (node (ref "R6") (pin "2") (pinfunction "2_2") (pintype "passive"))
    )
    (net (code "41") (name "Net-(U1-VBN)") (class "Default")
      (node (ref "C25") (pin "2") (pinfunction "2_2") (pintype "passive"))
      (node (ref "U1") (pin "31") (pinfunction "VBN_31") (pintype "input"))
    )
    (net (code "42") (name "Net-(U1-VBP)") (class "Default")
      (node (ref "C27") (pin "2") (pinfunction "2_2") (pintype "passive"))
      (node (ref "U1") (pin "32") (pinfunction "VBP_32") (pintype "input"))
    )
    (net (code "43") (name "Net-(U1-VCL)") (class "Default")
      (node (ref "C26") (pin "1") (pinfunction "1_1") (pintype "passive"))
      (node (ref "U1") (pin "21") (pinfunction "VCL_21") (pintype "input"))
    )
    (net (code "44") (name "Net-(U1-VCLH)") (class "Default")
      (node (ref "C24") (pin "1") (pinfunction "1_1") (pintype "passive"))
      (node (ref "U1") (pin "14") (pinfunction "VCLH_14") (pintype "input"))
    )
    (net (code "45") (name "Net-(U2-PR1)") (class "Default")
      (node (ref "R22") (pin "2") (pinfunction "2_2") (pintype "passive"))
      (node (ref "R23") (pin "1") (pinfunction "1_1") (pintype "passive"))
      (node (ref "U2") (pin "4") (pinfunction "PR1_4") (pintype "input"))
    )
    (net (code "46") (name "unconnected-(CON1-Pad4)") (class "Default")
      (node (ref "CON1") (pin "4") (pinfunction "4_4") (pintype "passive"))
    )
    (net (code "47") (name "unconnected-(R7-Pad2)") (class "Default")
      (node (ref "R7") (pin "2") (pinfunction "2_2") (pintype "passive"))
    )
    (net (code "48") (name "unconnected-(U1-EHMD-Pad30)") (class "Default")
      (node (ref "U1") (pin "30") (pinfunction "EHMD_30") (pintype "input"))
    )
    (net (code "49") (name "unconnected-(U1-EXTAL-Pad19)") (class "Default")
      (node (ref "U1") (pin "19") (pinfunction "EXTAL_19") (pintype "input"))
    )
    (net (code "50") (name "unconnected-(U1-NMI-Pad36)") (class "Default")
      (node (ref "U1") (pin "36") (pinfunction "NMI_36") (pintype "input"))
    )
    (net (code "51") (name "unconnected-(U1-P003-Pad132)") (class "Default")
      (node (ref "U1") (pin "132") (pinfunction "P003_132") (pintype "input"))
    )
    (net (code "52") (name "unconnected-(U1-P004-Pad131)") (class "Default")
      (node (ref "U1") (pin "131") (pinfunction "P004_131") (pintype "input"))
    )
    (net (code "53") (name "unconnected-(U1-P005-Pad130)") (class "Default")
      (node (ref "U1") (pin "130") (pinfunction "P005_130") (pintype "input"))
    )
    (net (code "54") (name "unconnected-(U1-P006-Pad129)") (class "Default")
      (node (ref "U1") (pin "129") (pinfunction "P006_129") (pintype "input"))
    )
    (net (code "55") (name "unconnected-(U1-P008-Pad126)") (class "Default")
      (node (ref "U1") (pin "126") (pinfunction "P008_126") (pintype "input"))
    )
    (net (code "56") (name "unconnected-(U1-P009-Pad125)") (class "Default")
      (node (ref "U1") (pin "125") (pinfunction "P009_125") (pintype "input"))
    )
    (net (code "57") (name "unconnected-(U1-P010-Pad123)") (class "Default")
      (node (ref "U1") (pin "123") (pinfunction "P010_123") (pintype "input"))
    )
    (net (code "58") (name "unconnected-(U1-P011-Pad122)") (class "Default")
      (node (ref "U1") (pin "122") (pinfunction "P011_122") (pintype "input"))
    )
    (net (code "59") (name "unconnected-(U1-P012-Pad121)") (class "Default")
      (node (ref "U1") (pin "121") (pinfunction "P012_121") (pintype "input"))
    )
    (net (code "60") (name "unconnected-(U1-P013-Pad120)") (class "Default")
      (node (ref "U1") (pin "120") (pinfunction "P013_120") (pintype "input"))
    )
    (net (code "61") (name "unconnected-(U1-P014-Pad119)") (class "Default")
      (node (ref "U1") (pin "119") (pinfunction "P014_119") (pintype "input"))
    )
    (net (code "62") (name "unconnected-(U1-P015-Pad118)") (class "Default")
      (node (ref "U1") (pin "118") (pinfunction "P015_118") (pintype "input"))
    )
    (net (code "63") (name "unconnected-(U1-P100-Pad99)") (class "Default")
      (node (ref "U1") (pin "99") (pinfunction "P100_99") (pintype "input"))
    )
    (net (code "64") (name "unconnected-(U1-P101-Pad98)") (class "Default")
      (node (ref "U1") (pin "98") (pinfunction "P101_98") (pintype "input"))
    )
    (net (code "65") (name "unconnected-(U1-P102-Pad97)") (class "Default")
      (node (ref "U1") (pin "97") (pinfunction "P102_97") (pintype "input"))
    )
    (net (code "66") (name "unconnected-(U1-P103-Pad96)") (class "Default")
      (node (ref "U1") (pin "96") (pinfunction "P103_96") (pintype "input"))
    )
    (net (code "67") (name "unconnected-(U1-P104-Pad95)") (class "Default")
      (node (ref "U1") (pin "95") (pinfunction "P104_95") (pintype "input"))
    )
    (net (code "68") (name "unconnected-(U1-P105-Pad94)") (class "Default")
      (node (ref "U1") (pin "94") (pinfunction "P105_94") (pintype "input"))
    )
    (net (code "69") (name "unconnected-(U1-P106-Pad93)") (class "Default")
      (node (ref "U1") (pin "93") (pinfunction "P106_93") (pintype "input"))
    )
    (net (code "70") (name "unconnected-(U1-P107-Pad92)") (class "Default")
      (node (ref "U1") (pin "92") (pinfunction "P107_92") (pintype "input"))
    )
    (net (code "71") (name "unconnected-(U1-P108-Pad1)") (class "Default")
      (node (ref "U1") (pin "1") (pinfunction "P108_1") (pintype "input"))
    )
    (net (code "72") (name "unconnected-(U1-P108-Pad89)") (class "Default")
      (node (ref "U1") (pin "89") (pinfunction "P108_89") (pintype "input"))
    )
    (net (code "73") (name "unconnected-(U1-P109-Pad88)") (class "Default")
      (node (ref "U1") (pin "88") (pinfunction "P109_88") (pintype "input"))
    )
    (net (code "74") (name "unconnected-(U1-P110-Pad87)") (class "Default")
      (node (ref "U1") (pin "87") (pinfunction "P110_87") (pintype "input"))
    )
    (net (code "75") (name "unconnected-(U1-P111-Pad86)") (class "Default")
      (node (ref "U1") (pin "86") (pinfunction "P111_86") (pintype "input"))
    )
    (net (code "76") (name "unconnected-(U1-P112-Pad85)") (class "Default")
      (node (ref "U1") (pin "85") (pinfunction "P112_85") (pintype "input"))
    )
    (net (code "77") (name "unconnected-(U1-P113-Pad84)") (class "Default")
      (node (ref "U1") (pin "84") (pinfunction "P113_84") (pintype "input"))
    )
    (net (code "78") (name "unconnected-(U1-P202-Pad49)") (class "Default")
      (node (ref "U1") (pin "49") (pinfunction "P202_49") (pintype "input"))
    )
    (net (code "79") (name "unconnected-(U1-P203-Pad48)") (class "Default")
      (node (ref "U1") (pin "48") (pinfunction "P203_48") (pintype "input"))
    )
    (net (code "80") (name "unconnected-(U1-P204-Pad47)") (class "Default")
      (node (ref "U1") (pin "47") (pinfunction "P204_47") (pintype "input"))
    )
    (net (code "81") (name "unconnected-(U1-P205-Pad46)") (class "Default")
      (node (ref "U1") (pin "46") (pinfunction "P205_46") (pintype "input"))
    )
    (net (code "82") (name "unconnected-(U1-P300-Pad72)") (class "Default")
      (node (ref "U1") (pin "72") (pinfunction "P300_72") (pintype "input"))
    )
    (net (code "83") (name "unconnected-(U1-P301-Pad71)") (class "Default")
      (node (ref "U1") (pin "71") (pinfunction "P301_71") (pintype "input"))
    )
    (net (code "84") (name "unconnected-(U1-P302-Pad70)") (class "Default")
      (node (ref "U1") (pin "70") (pinfunction "P302_70") (pintype "input"))
    )
    (net (code "85") (name "unconnected-(U1-P304-Pad68)") (class "Default")
      (node (ref "U1") (pin "68") (pinfunction "P304_68") (pintype "input"))
    )
    (net (code "86") (name "unconnected-(U1-P305-Pad65)") (class "Default")
      (node (ref "U1") (pin "65") (pinfunction "P305_65") (pintype "input"))
    )
    (net (code "87") (name "unconnected-(U1-P306-Pad64)") (class "Default")
      (node (ref "U1") (pin "64") (pinfunction "P306_64") (pintype "input"))
    )
    (net (code "88") (name "unconnected-(U1-P307-Pad63)") (class "Default")
      (node (ref "U1") (pin "63") (pinfunction "P307_63") (pintype "input"))
    )
    (net (code "89") (name "unconnected-(U1-P308-Pad62)") (class "Default")
      (node (ref "U1") (pin "62") (pinfunction "P308_62") (pintype "input"))
    )
    (net (code "90") (name "unconnected-(U1-P309-Pad61)") (class "Default")
      (node (ref "U1") (pin "61") (pinfunction "P309_61") (pintype "input"))
    )
    (net (code "91") (name "unconnected-(U1-P310-Pad60)") (class "Default")
      (node (ref "U1") (pin "60") (pinfunction "P310_60") (pintype "input"))
    )
    (net (code "92") (name "unconnected-(U1-P311-Pad59)") (class "Default")
      (node (ref "U1") (pin "59") (pinfunction "P311_59") (pintype "input"))
    )
    (net (code "93") (name "unconnected-(U1-P312-Pad58)") (class "Default")
      (node (ref "U1") (pin "58") (pinfunction "P312_58") (pintype "input"))
    )
    (net (code "94") (name "unconnected-(U1-P313-Pad57)") (class "Default")
      (node (ref "U1") (pin "57") (pinfunction "P313_57") (pintype "input"))
    )
    (net (code "95") (name "unconnected-(U1-P314-Pad56)") (class "Default")
      (node (ref "U1") (pin "56") (pinfunction "P314_56") (pintype "input"))
    )
    (net (code "96") (name "unconnected-(U1-P405-Pad28)") (class "Default")
      (node (ref "U1") (pin "28") (pinfunction "P405_28") (pintype "input"))
    )
    (net (code "97") (name "unconnected-(U1-P406-Pad27)") (class "Default")
      (node (ref "U1") (pin "27") (pinfunction "P406_27") (pintype "input"))
    )
    (net (code "98") (name "unconnected-(U1-P407-Pad26)") (class "Default")
      (node (ref "U1") (pin "26") (pinfunction "P407_26") (pintype "input"))
    )
    (net (code "99") (name "unconnected-(U1-P408-Pad25)") (class "Default")
      (node (ref "U1") (pin "25") (pinfunction "P408_25") (pintype "input"))
    )
    (net (code "100") (name "unconnected-(U1-P410-Pad23)") (class "Default")
      (node (ref "U1") (pin "23") (pinfunction "P410_23") (pintype "input"))
    )
    (net (code "101") (name "unconnected-(U1-P500-Pad115)") (class "Default")
      (node (ref "U1") (pin "115") (pinfunction "P500_115") (pintype "input"))
    )
    (net (code "102") (name "unconnected-(U1-P502-Pad113)") (class "Default")
      (node (ref "U1") (pin "113") (pinfunction "P502_113") (pintype "input"))
    )
    (net (code "103") (name "unconnected-(U1-P503-Pad112)") (class "Default")
      (node (ref "U1") (pin "112") (pinfunction "P503_112") (pintype "input"))
    )
    (net (code "104") (name "unconnected-(U1-P504-Pad111)") (class "Default")
      (node (ref "U1") (pin "111") (pinfunction "P504_111") (pintype "input"))
    )
    (net (code "105") (name "unconnected-(U1-P505-Pad110)") (class "Default")
      (node (ref "U1") (pin "110") (pinfunction "P505_110") (pintype "input"))
    )
    (net (code "106") (name "unconnected-(U1-P506-Pad109)") (class "Default")
      (node (ref "U1") (pin "109") (pinfunction "P506_109") (pintype "input"))
    )
    (net (code "107") (name "unconnected-(U1-P508-Pad107)") (class "Default")
      (node (ref "U1") (pin "107") (pinfunction "P508_107") (pintype "input"))
    )
    (net (code "108") (name "unconnected-(U1-P512-Pad103)") (class "Default")
      (node (ref "U1") (pin "103") (pinfunction "P512_103") (pintype "input"))
    )
    (net (code "109") (name "unconnected-(U1-P513-Pad102)") (class "Default")
      (node (ref "U1") (pin "102") (pinfunction "P513_102") (pintype "input"))
    )
    (net (code "110") (name "unconnected-(U1-P514-Pad101)") (class "Default")
      (node (ref "U1") (pin "101") (pinfunction "P514_101") (pintype "input"))
    )
    (net (code "111") (name "unconnected-(U1-P600-Pad83)") (class "Default")
      (node (ref "U1") (pin "83") (pinfunction "P600_83") (pintype "input"))
    )
    (net (code "112") (name "unconnected-(U1-P601-Pad82)") (class "Default")
      (node (ref "U1") (pin "82") (pinfunction "P601_82") (pintype "input"))
    )
    (net (code "113") (name "unconnected-(U1-P602-Pad81)") (class "Default")
      (node (ref "U1") (pin "81") (pinfunction "P602_81") (pintype "input"))
    )
    (net (code "114") (name "unconnected-(U1-P604-Pad79)") (class "Default")
      (node (ref "U1") (pin "79") (pinfunction "P604_79") (pintype "input"))
    )
    (net (code "115") (name "unconnected-(U1-P605-Pad78)") (class "Default")
      (node (ref "U1") (pin "78") (pinfunction "P605_78") (pintype "input"))
    )
    (net (code "116") (name "unconnected-(U1-P606-Pad77)") (class "Default")
      (node (ref "U1") (pin "77") (pinfunction "P606_77") (pintype "input"))
    )
    (net (code "117") (name "unconnected-(U1-P607-Pad76)") (class "Default")
      (node (ref "U1") (pin "76") (pinfunction "P607_76") (pintype "input"))
    )
    (net (code "118") (name "unconnected-(U1-P608-Pad75)") (class "Default")
      (node (ref "U1") (pin "75") (pinfunction "P608_75") (pintype "input"))
    )
    (net (code "119") (name "unconnected-(U1-P609-Pad74)") (class "Default")
      (node (ref "U1") (pin "74") (pinfunction "P609_74") (pintype "input"))
    )
    (net (code "120") (name "unconnected-(U1-P610-Pad73)") (class "Default")
      (node (ref "U1") (pin "73") (pinfunction "P610_73") (pintype "input"))
    )
    (net (code "121") (name "unconnected-(U1-P700-Pad54)") (class "Default")
      (node (ref "U1") (pin "54") (pinfunction "P700_54") (pintype "input"))
    )
    (net (code "122") (name "unconnected-(U1-P701-Pad53)") (class "Default")
      (node (ref "U1") (pin "53") (pinfunction "P701_53") (pintype "input"))
    )
    (net (code "123") (name "unconnected-(U1-P702-Pad52)") (class "Default")
      (node (ref "U1") (pin "52") (pinfunction "P702_52") (pintype "input"))
    )
    (net (code "124") (name "unconnected-(U1-P703-Pad51)") (class "Default")
      (node (ref "U1") (pin "51") (pinfunction "P703_51") (pintype "input"))
    )
    (net (code "125") (name "unconnected-(U1-P704-Pad50)") (class "Default")
      (node (ref "U1") (pin "50") (pinfunction "P704_50") (pintype "input"))
    )
    (net (code "126") (name "unconnected-(U1-P800-Pad13)") (class "Default")
      (node (ref "U1") (pin "13") (pinfunction "P800_13") (pintype "input"))
    )
    (net (code "127") (name "unconnected-(U1-P801-Pad12)") (class "Default")
      (node (ref "U1") (pin "12") (pinfunction "P801_12") (pintype "input"))
    )
    (net (code "128") (name "unconnected-(U1-P802-Pad11)") (class "Default")
      (node (ref "U1") (pin "11") (pinfunction "P802_11") (pintype "input"))
    )
    (net (code "129") (name "unconnected-(U1-P803-Pad10)") (class "Default")
      (node (ref "U1") (pin "10") (pinfunction "P803_10") (pintype "input"))
    )
    (net (code "130") (name "unconnected-(U1-P804-Pad9)") (class "Default")
      (node (ref "U1") (pin "9") (pinfunction "P804_9") (pintype "input"))
    )
    (net (code "131") (name "unconnected-(U1-P805-Pad8)") (class "Default")
      (node (ref "U1") (pin "8") (pinfunction "P805_8") (pintype "input"))
    )
    (net (code "132") (name "unconnected-(U1-P806-Pad7)") (class "Default")
      (node (ref "U1") (pin "7") (pinfunction "P806_7") (pintype "input"))
    )
    (net (code "133") (name "unconnected-(U1-P807-Pad6)") (class "Default")
      (node (ref "U1") (pin "6") (pinfunction "P807_6") (pintype "input"))
    )
    (net (code "134") (name "unconnected-(U1-P808-Pad5)") (class "Default")
      (node (ref "U1") (pin "5") (pinfunction "P808_5") (pintype "input"))
    )
    (net (code "135") (name "unconnected-(U1-P809-Pad4)") (class "Default")
      (node (ref "U1") (pin "4") (pinfunction "P809_4") (pintype "input"))
    )
    (net (code "136") (name "unconnected-(U1-P811-Pad144)") (class "Default")
      (node (ref "U1") (pin "144") (pinfunction "P811_144") (pintype "input"))
    )
    (net (code "137") (name "unconnected-(U1-P812-Pad143)") (class "Default")
      (node (ref "U1") (pin "143") (pinfunction "P812_143") (pintype "input"))
    )
    (net (code "138") (name "unconnected-(U1-P813-Pad142)") (class "Default")
      (node (ref "U1") (pin "142") (pinfunction "P813_142") (pintype "input"))
    )
    (net (code "139") (name "unconnected-(U1-P814-Pad141)") (class "Default")
      (node (ref "U1") (pin "141") (pinfunction "P814_141") (pintype "input"))
    )
    (net (code "140") (name "unconnected-(U1-P815-Pad140)") (class "Default")
      (node (ref "U1") (pin "140") (pinfunction "P815_140") (pintype "input"))
    )
    (net (code "141") (name "unconnected-(U1-USB_DM-Pad43)") (class "Default")
      (node (ref "U1") (pin "43") (pinfunction "USB_DM_43") (pintype "input"))
    )
    (net (code "142") (name "unconnected-(U1-USB_DP-Pad44)") (class "Default")
      (node (ref "U1") (pin "44") (pinfunction "USB_DP_44") (pintype "input"))
    )
    (net (code "143") (name "unconnected-(U1-VBAT_EHC-Pad39)") (class "Default")
      (node (ref "U1") (pin "39") (pinfunction "VBAT_EHC_39") (pintype "input"))
    )
    (net (code "144") (name "unconnected-(U1-VSS-Pad2)") (class "Default")
      (node (ref "U1") (pin "2") (pinfunction "VSS_2") (pintype "input"))
    )
    (net (code "145") (name "unconnected-(U1-XCIN-Pad16)") (class "Default")
      (node (ref "U1") (pin "16") (pinfunction "XCIN_16") (pintype "input"))
    )
    (net (code "146") (name "unconnected-(U1-XCOUT-Pad15)") (class "Default")
      (node (ref "U1") (pin "15") (pinfunction "XCOUT_15") (pintype "input"))
    )
    (net (code "147") (name "unconnected-(U1-XTAL-Pad18)") (class "Default")
      (node (ref "U1") (pin "18") (pinfunction "XTAL_18") (pintype "input"))
    )
  )
)
